# pripravekV2.net
KiCad netlist of a schematic drawn in EAGLE
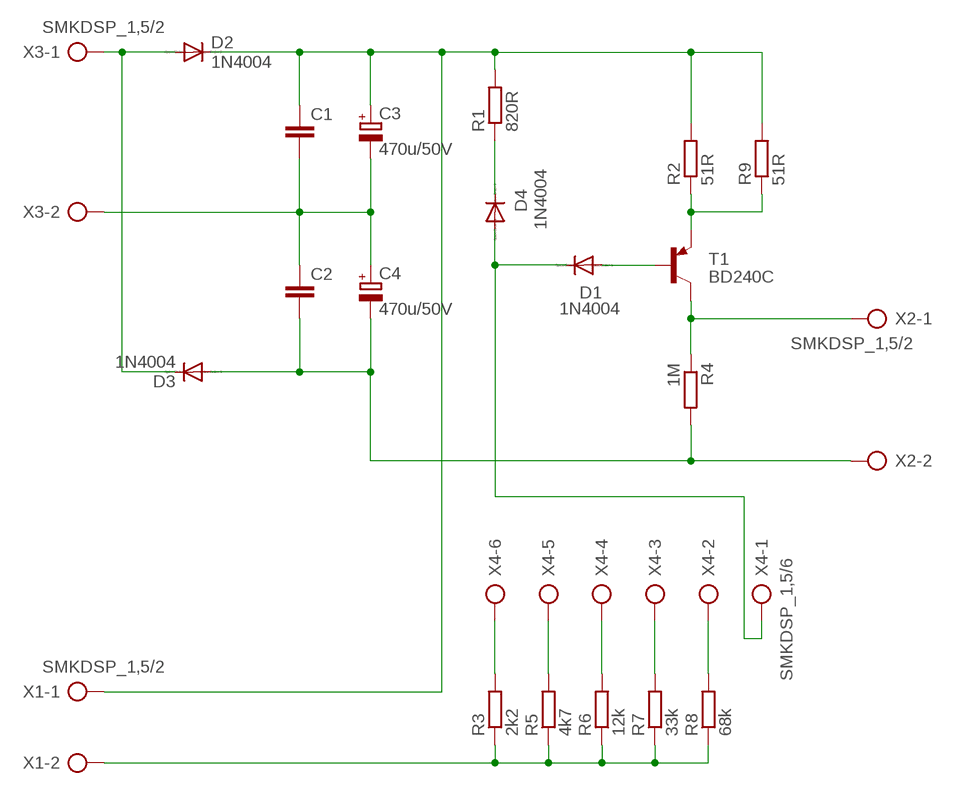
[diagram p0: schematic, sheet 1]

(export (version "E")
  (design (tool "Eeschema 10.0.6"))
  (components
    (comp (ref "C1")
      (value "C-EU050-035X075")
      (footprint "eagle-import:C050-035X075")
      (libsource (lib "eagle-import") (part "C-EU050-035X075"))
    )
    (comp (ref "C2")
      (value "C-EU050-035X075")
      (footprint "eagle-import:C050-035X075")
      (libsource (lib "eagle-import") (part "C-EU050-035X075"))
    )
    (comp (ref "C3")
      (value "470u/50V")
      (footprint "eagle-import:E5-13")
      (libsource (lib "eagle-import") (part "CPOL-EUE5-13"))
    )
    (comp (ref "C4")
      (value "470u/50V")
      (footprint "eagle-import:E5-13")
      (libsource (lib "eagle-import") (part "CPOL-EUE5-13"))
    )
    (comp (ref "D1")
      (value "1N4004")
      (footprint "eagle-import:DO41-10")
      (libsource (lib "eagle-import") (part "1N4004"))
    )
    (comp (ref "D2")
      (value "1N4004")
      (footprint "eagle-import:DO41-10")
      (libsource (lib "eagle-import") (part "1N4004"))
    )
    (comp (ref "D3")
      (value "1N4004")
      (footprint "eagle-import:DO41-10")
      (libsource (lib "eagle-import") (part "1N4004"))
    )
    (comp (ref "D4")
      (value "1N4004")
      (footprint "eagle-import:DO41-10")
      (libsource (lib "eagle-import") (part "1N4004"))
    )
    (comp (ref "R1")
      (value "820R")
      (footprint "eagle-import:P0817_22")
      (libsource (lib "eagle-import") (part "R-EU_0817/22"))
    )
    (comp (ref "R2")
      (value "51R")
      (footprint "eagle-import:P0817_22")
      (libsource (lib "eagle-import") (part "R-EU_0817/22"))
    )
    (comp (ref "R3")
      (value "2k2")
      (footprint "eagle-import:P0817_22")
      (libsource (lib "eagle-import") (part "R-EU_0817/22"))
    )
    (comp (ref "R4")
      (value "1M")
      (footprint "eagle-import:0207_12")
      (libsource (lib "eagle-import") (part "R-EU_0207/12"))
    )
    (comp (ref "R5")
      (value "4k7")
      (footprint "eagle-import:P0817_22")
      (libsource (lib "eagle-import") (part "R-EU_0817/22"))
    )
    (comp (ref "R6")
      (value "12k")
      (footprint "eagle-import:P0817_22")
      (libsource (lib "eagle-import") (part "R-EU_0817/22"))
    )
    (comp (ref "R7")
      (value "33k")
      (footprint "eagle-import:P0817_22")
      (libsource (lib "eagle-import") (part "R-EU_0817/22"))
    )
    (comp (ref "R8")
      (value "68k")
      (footprint "eagle-import:P0817_22")
      (libsource (lib "eagle-import") (part "R-EU_0817/22"))
    )
    (comp (ref "R9")
      (value "51R")
      (footprint "eagle-import:P0817_22")
      (libsource (lib "eagle-import") (part "R-EU_0817/22"))
    )
    (comp (ref "T1")
      (value "BD240C")
      (footprint "eagle-import:TO220")
      (libsource (lib "eagle-import") (part "-PNP-TO220"))
    )
    (comp (ref "X1")
      (value "SMKDSP_1,5/2")
      (footprint "eagle-import:SMKDSP_1,5_2")
      (fields (field (name "MF") "FARNELL") (field (name "MPN") "1733570"))
      (libsource (lib "eagle-import") (part "SMKDSP_1,5/2"))
    )
    (comp (ref "X2")
      (value "SMKDSP_1,5/2")
      (footprint "eagle-import:SMKDSP_1,5_2")
      (fields (field (name "MF") "FARNELL") (field (name "MPN") "1733570"))
      (libsource (lib "eagle-import") (part "SMKDSP_1,5/2"))
    )
    (comp (ref "X3")
      (value "SMKDSP_1,5/2")
      (footprint "eagle-import:SMKDSP_1,5_2")
      (fields (field (name "MF") "FARNELL") (field (name "MPN") "1733570"))
      (libsource (lib "eagle-import") (part "SMKDSP_1,5/2"))
    )
    (comp (ref "X4")
      (value "SMKDSP_1,5/6")
      (footprint "eagle-import:SMKDSP_1,5_6")
      (fields (field (name "MF") "FARNELL") (field (name "MPN") "1733619"))
      (libsource (lib "eagle-import") (part "SMKDSP_1,5/6"))
    )
  )
  (nets
    (net (code "1") (name "Net-(D4-PadC)") (class "Default")
      (node (ref "D4") (pin "C") (pinfunction "C_C") (pintype "passive"))
      (node (ref "R1") (pin "1") (pinfunction "1_1") (pintype "passive"))
    )
    (net (code "2") (name "Net-(T1-B)") (class "Default")
      (node (ref "D1") (pin "A") (pinfunction "A_A") (pintype "passive"))
      (node (ref "T1") (pin "1") (pinfunction "B_1") (pintype "passive"))
    )
    (net (code "3") (name "Net-(T1-C)") (class "Default")
      (node (ref "R4") (pin "1") (pinfunction "1_1") (pintype "passive"))
      (node (ref "T1") (pin "2") (pinfunction "C_2") (pintype "passive"))
      (node (ref "X2") (pin "1") (pinfunction "KL_1") (pintype "passive"))
    )
    (net (code "4") (name "Net-(T1-E)") (class "Default")
      (node (ref "R2") (pin "1") (pinfunction "1_1") (pintype "passive"))
      (node (ref "R9") (pin "1") (pinfunction "1_1") (pintype "passive"))
      (node (ref "T1") (pin "3") (pinfunction "E_3") (pintype "passive"))
    )
    (net (code "5") (name "Net-(X1A-KL)") (class "Default")
      (node (ref "C1") (pin "1") (pinfunction "1_1") (pintype "passive"))
      (node (ref "C3") (pin "+") (pinfunction "+_+") (pintype "passive"))
      (node (ref "D2") (pin "C") (pinfunction "C_C") (pintype "passive"))
      (node (ref "R1") (pin "2") (pinfunction "2_2") (pintype "passive"))
      (node (ref "R2") (pin "2") (pinfunction "2_2") (pintype "passive"))
      (node (ref "R9") (pin "2") (pinfunction "2_2") (pintype "passive"))
      (node (ref "X1") (pin "1") (pinfunction "KL_1") (pintype "passive"))
    )
    (net (code "6") (name "Net-(X1B-KL)") (class "Default")
      (node (ref "R3") (pin "1") (pinfunction "1_1") (pintype "passive"))
      (node (ref "R5") (pin "1") (pinfunction "1_1") (pintype "passive"))
      (node (ref "R6") (pin "1") (pinfunction "1_1") (pintype "passive"))
      (node (ref "R7") (pin "1") (pinfunction "1_1") (pintype "passive"))
      (node (ref "R8") (pin "1") (pinfunction "1_1") (pintype "passive"))
      (node (ref "X1") (pin "2") (pinfunction "KL_2") (pintype "passive"))
    )
    (net (code "7") (name "Net-(X2B-KL)") (class "Default")
      (node (ref "C2") (pin "2") (pinfunction "2_2") (pintype "passive"))
      (node (ref "C4") (pin "-") (pinfunction "-_-") (pintype "passive"))
      (node (ref "D3") (pin "A") (pinfunction "A_A") (pintype "passive"))
      (node (ref "R4") (pin "2") (pinfunction "2_2") (pintype "passive"))
      (node (ref "X2") (pin "2") (pinfunction "KL_2") (pintype "passive"))
    )
    (net (code "8") (name "Net-(X3A-KL)") (class "Default")
      (node (ref "D2") (pin "A") (pinfunction "A_A") (pintype "passive"))
      (node (ref "D3") (pin "C") (pinfunction "C_C") (pintype "passive"))
      (node (ref "X3") (pin "1") (pinfunction "KL_1") (pintype "passive"))
    )
    (net (code "9") (name "Net-(X3B-KL)") (class "Default")
      (node (ref "C1") (pin "2") (pinfunction "2_2") (pintype "passive"))
      (node (ref "C2") (pin "1") (pinfunction "1_1") (pintype "passive"))
      (node (ref "C3") (pin "-") (pinfunction "-_-") (pintype "passive"))
      (node (ref "C4") (pin "+") (pinfunction "+_+") (pintype "passive"))
      (node (ref "X3") (pin "2") (pinfunction "KL_2") (pintype "passive"))
    )
    (net (code "10") (name "Net-(X4A-KL)") (class "Default")
      (node (ref "D1") (pin "C") (pinfunction "C_C") (pintype "passive"))
      (node (ref "D4") (pin "A") (pinfunction "A_A") (pintype "passive"))
      (node (ref "X4") (pin "1") (pinfunction "KL_1") (pintype "passive"))
    )
    (net (code "11") (name "Net-(X4B-KL)") (class "Default")
      (node (ref "R8") (pin "2") (pinfunction "2_2") (pintype "passive"))
      (node (ref "X4") (pin "2") (pinfunction "KL_2") (pintype "passive"))
    )
    (net (code "12") (name "Net-(X4C-KL)") (class "Default")
      (node (ref "R7") (pin "2") (pinfunction "2_2") (pintype "passive"))
      (node (ref "X4") (pin "3") (pinfunction "KL_3") (pintype "passive"))
    )
    (net (code "13") (name "Net-(X4D-KL)") (class "Default")
      (node (ref "R6") (pin "2") (pinfunction "2_2") (pintype "passive"))
      (node (ref "X4") (pin "4") (pinfunction "KL_4") (pintype "passive"))
    )
    (net (code "14") (name "Net-(X4E-KL)") (class "Default")
      (node (ref "R5") (pin "2") (pinfunction "2_2") (pintype "passive"))
      (node (ref "X4") (pin "5") (pinfunction "KL_5") (pintype "passive"))
    )
    (net (code "15") (name "Net-(X4F-KL)") (class "Default")
      (node (ref "R3") (pin "2") (pinfunction "2_2") (pintype "passive"))
      (node (ref "X4") (pin "6") (pinfunction "KL_6") (pintype "passive"))
    )
  )
)
